# schema.net
KiCad netlist of a schematic drawn in EAGLE
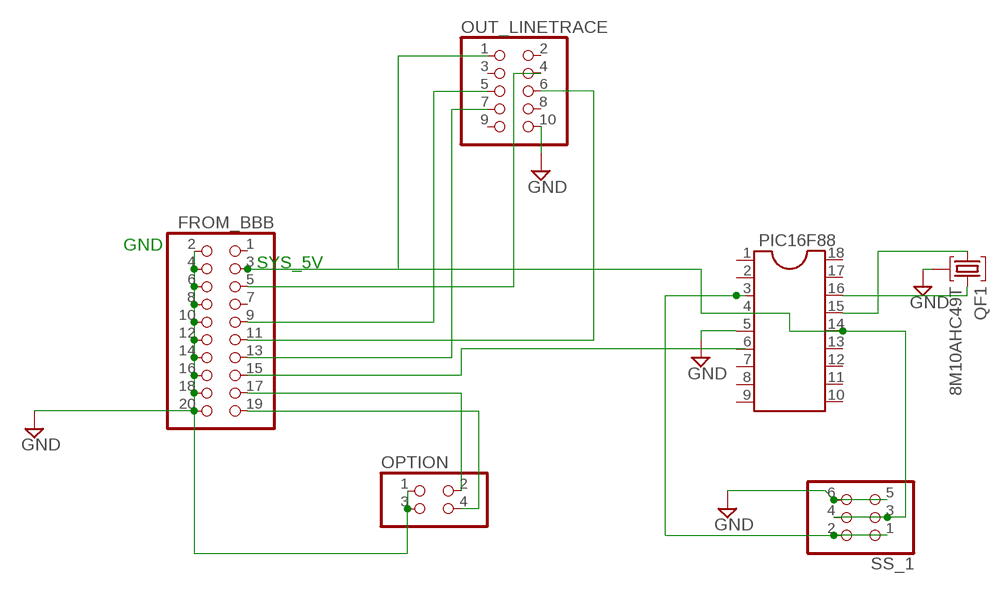
[diagram p0: schematic, sheet 1]

(export (version "E")
  (design (tool "Eeschema 10.0.6"))
  (components
    (comp (ref "FROM_BBB")
      (value "PINHD-2X10")
      (footprint "eagle-import:2X10")
      (libsource (lib "eagle-import") (part "PINHD-2X10"))
    )
    (comp (ref "OPTION")
      (value "PINHD-2X2")
      (footprint "eagle-import:2X02")
      (libsource (lib "eagle-import") (part "PINHD-2X2"))
    )
    (comp (ref "OUT_LINETRACE")
      (value "PINHD-2X5")
      (footprint "eagle-import:2X05")
      (libsource (lib "eagle-import") (part "PINHD-2X5"))
    )
    (comp (ref "PIC16F88")
      (value "DIL18S")
      (footprint "eagle-import:SOCKET-18")
      (libsource (lib "eagle-import") (part "DIL18S"))
    )
    (comp (ref "QF1")
      (value "8M10AHC49T")
      (footprint "eagle-import:HC49U")
      (libsource (lib "eagle-import") (part "8M10AHC49T"))
    )
    (comp (ref "SS_1")
      (value "PINHD-2X3")
      (footprint "eagle-import:2X03")
      (libsource (lib "eagle-import") (part "PINHD-2X3"))
    )
  )
  (nets
    (net (code "1") (name "GND") (class "Default")
      (node (ref "FROM_BBB") (pin "10") (pinfunction "10_10") (pintype "passive"))
      (node (ref "FROM_BBB") (pin "12") (pinfunction "12_12") (pintype "passive"))
      (node (ref "FROM_BBB") (pin "14") (pinfunction "14_14") (pintype "passive"))
      (node (ref "FROM_BBB") (pin "16") (pinfunction "16_16") (pintype "passive"))
      (node (ref "FROM_BBB") (pin "18") (pinfunction "18_18") (pintype "passive"))
      (node (ref "FROM_BBB") (pin "2") (pinfunction "2_2") (pintype "passive"))
      (node (ref "FROM_BBB") (pin "20") (pinfunction "20_20") (pintype "passive"))
      (node (ref "FROM_BBB") (pin "4") (pinfunction "4_4") (pintype "passive"))
      (node (ref "FROM_BBB") (pin "6") (pinfunction "6_6") (pintype "passive"))
      (node (ref "FROM_BBB") (pin "8") (pinfunction "8_8") (pintype "passive"))
      (node (ref "OPTION") (pin "1") (pinfunction "1_1") (pintype "passive"))
      (node (ref "OPTION") (pin "3") (pinfunction "3_3") (pintype "passive"))
      (node (ref "OUT_LINETRACE") (pin "10") (pinfunction "10_10") (pintype "passive"))
      (node (ref "PIC16F88") (pin "5") (pinfunction "5_5") (pintype "passive"))
      (node (ref "QF1") (pin "2") (pinfunction "2_2") (pintype "passive"))
      (node (ref "SS_1") (pin "5") (pinfunction "5_5") (pintype "passive"))
      (node (ref "SS_1") (pin "6") (pinfunction "6_6") (pintype "passive"))
    )
    (net (code "2") (name "Net-(FROM_BBB-Pad3)") (class "Default")
      (node (ref "FROM_BBB") (pin "3") (pinfunction "3_3") (pintype "passive"))
      (node (ref "OUT_LINETRACE") (pin "1") (pinfunction "1_1") (pintype "passive"))
      (node (ref "PIC16F88") (pin "14") (pinfunction "14_14") (pintype "passive"))
      (node (ref "PIC16F88") (pin "4") (pinfunction "4_4") (pintype "passive"))
      (node (ref "SS_1") (pin "3") (pinfunction "3_3") (pintype "passive"))
      (node (ref "SS_1") (pin "4") (pinfunction "4_4") (pintype "passive"))
    )
    (net (code "3") (name "Net-(FROM_BBB-Pad5)") (class "Default")
      (node (ref "FROM_BBB") (pin "5") (pinfunction "5_5") (pintype "passive"))
      (node (ref "OUT_LINETRACE") (pin "4") (pinfunction "4_4") (pintype "passive"))
    )
    (net (code "4") (name "Net-(FROM_BBB-Pad9)") (class "Default")
      (node (ref "FROM_BBB") (pin "9") (pinfunction "9_9") (pintype "passive"))
      (node (ref "OUT_LINETRACE") (pin "5") (pinfunction "5_5") (pintype "passive"))
    )
    (net (code "5") (name "Net-(FROM_BBB-Pad11)") (class "Default")
      (node (ref "FROM_BBB") (pin "11") (pinfunction "11_11") (pintype "passive"))
      (node (ref "OUT_LINETRACE") (pin "6") (pinfunction "6_6") (pintype "passive"))
    )
    (net (code "6") (name "Net-(FROM_BBB-Pad13)") (class "Default")
      (node (ref "FROM_BBB") (pin "13") (pinfunction "13_13") (pintype "passive"))
      (node (ref "OUT_LINETRACE") (pin "7") (pinfunction "7_7") (pintype "passive"))
    )
    (net (code "7") (name "Net-(FROM_BBB-Pad17)") (class "Default")
      (node (ref "FROM_BBB") (pin "17") (pinfunction "17_17") (pintype "passive"))
      (node (ref "OPTION") (pin "2") (pinfunction "2_2") (pintype "passive"))
    )
    (net (code "8") (name "Net-(FROM_BBB-Pad19)") (class "Default")
      (node (ref "FROM_BBB") (pin "19") (pinfunction "19_19") (pintype "passive"))
      (node (ref "OPTION") (pin "4") (pinfunction "4_4") (pintype "passive"))
    )
    (net (code "9") (name "Net-(PIC16F88-Pad3)") (class "Default")
      (node (ref "PIC16F88") (pin "3") (pinfunction "3_3") (pintype "passive"))
      (node (ref "SS_1") (pin "1") (pinfunction "1_1") (pintype "passive"))
      (node (ref "SS_1") (pin "2") (pinfunction "2_2") (pintype "passive"))
    )
    (net (code "10") (name "Net-(PIC16F88-Pad15)") (class "Default")
      (node (ref "PIC16F88") (pin "15") (pinfunction "15_15") (pintype "passive"))
      (node (ref "QF1") (pin "1") (pinfunction "1_1") (pintype "passive"))
    )
    (net (code "11") (name "Net-(PIC16F88-Pad16)") (class "Default")
      (node (ref "PIC16F88") (pin "16") (pinfunction "16_16") (pintype "passive"))
      (node (ref "QF1") (pin "3") (pinfunction "3_3") (pintype "passive"))
    )
    (net (code "12") (name "unconnected-(FROM_BBB-Pad1)") (class "Default")
      (node (ref "FROM_BBB") (pin "1") (pinfunction "1_1") (pintype "passive"))
    )
    (net (code "13") (name "unconnected-(FROM_BBB-Pad7)") (class "Default")
      (node (ref "FROM_BBB") (pin "7") (pinfunction "7_7") (pintype "passive"))
    )
    (net (code "14") (name "unconnected-(FROM_BBB-Pad15)") (class "Default")
      (node (ref "FROM_BBB") (pin "15") (pinfunction "15_15") (pintype "passive"))
    )
    (net (code "15") (name "unconnected-(OUT_LINETRACE-Pad2)") (class "Default")
      (node (ref "OUT_LINETRACE") (pin "2") (pinfunction "2_2") (pintype "passive"))
    )
    (net (code "16") (name "unconnected-(OUT_LINETRACE-Pad3)") (class "Default")
      (node (ref "OUT_LINETRACE") (pin "3") (pinfunction "3_3") (pintype "passive"))
    )
    (net (code "17") (name "unconnected-(OUT_LINETRACE-Pad8)") (class "Default")
      (node (ref "OUT_LINETRACE") (pin "8") (pinfunction "8_8") (pintype "passive"))
    )
    (net (code "18") (name "unconnected-(OUT_LINETRACE-Pad9)") (class "Default")
      (node (ref "OUT_LINETRACE") (pin "9") (pinfunction "9_9") (pintype "passive"))
    )
    (net (code "19") (name "unconnected-(PIC16F88-Pad1)") (class "Default")
      (node (ref "PIC16F88") (pin "1") (pinfunction "1_1") (pintype "passive"))
    )
    (net (code "20") (name "unconnected-(PIC16F88-Pad2)") (class "Default")
      (node (ref "PIC16F88") (pin "2") (pinfunction "2_2") (pintype "passive"))
    )
    (net (code "21") (name "unconnected-(PIC16F88-Pad6)") (class "Default")
      (node (ref "PIC16F88") (pin "6") (pinfunction "6_6") (pintype "passive"))
    )
    (net (code "22") (name "unconnected-(PIC16F88-Pad7)") (class "Default")
      (node (ref "PIC16F88") (pin "7") (pinfunction "7_7") (pintype "passive"))
    )
    (net (code "23") (name "unconnected-(PIC16F88-Pad8)") (class "Default")
      (node (ref "PIC16F88") (pin "8") (pinfunction "8_8") (pintype "passive"))
    )
    (net (code "24") (name "unconnected-(PIC16F88-Pad9)") (class "Default")
      (node (ref "PIC16F88") (pin "9") (pinfunction "9_9") (pintype "passive"))
    )
    (net (code "25") (name "unconnected-(PIC16F88-Pad10)") (class "Default")
      (node (ref "PIC16F88") (pin "10") (pinfunction "10_10") (pintype "passive"))
    )
    (net (code "26") (name "unconnected-(PIC16F88-Pad11)") (class "Default")
      (node (ref "PIC16F88") (pin "11") (pinfunction "11_11") (pintype "passive"))
    )
    (net (code "27") (name "unconnected-(PIC16F88-Pad12)") (class "Default")
      (node (ref "PIC16F88") (pin "12") (pinfunction "12_12") (pintype "passive"))
    )
    (net (code "28") (name "unconnected-(PIC16F88-Pad13)") (class "Default")
      (node (ref "PIC16F88") (pin "13") (pinfunction "13_13") (pintype "passive"))
    )
    (net (code "29") (name "unconnected-(PIC16F88-Pad17)") (class "Default")
      (node (ref "PIC16F88") (pin "17") (pinfunction "17_17") (pintype "passive"))
    )
    (net (code "30") (name "unconnected-(PIC16F88-Pad18)") (class "Default")
      (node (ref "PIC16F88") (pin "18") (pinfunction "18_18") (pintype "passive"))
    )
  )
)
